# microdevel_actel.net
KiCad netlist of a schematic drawn in Altium Designer
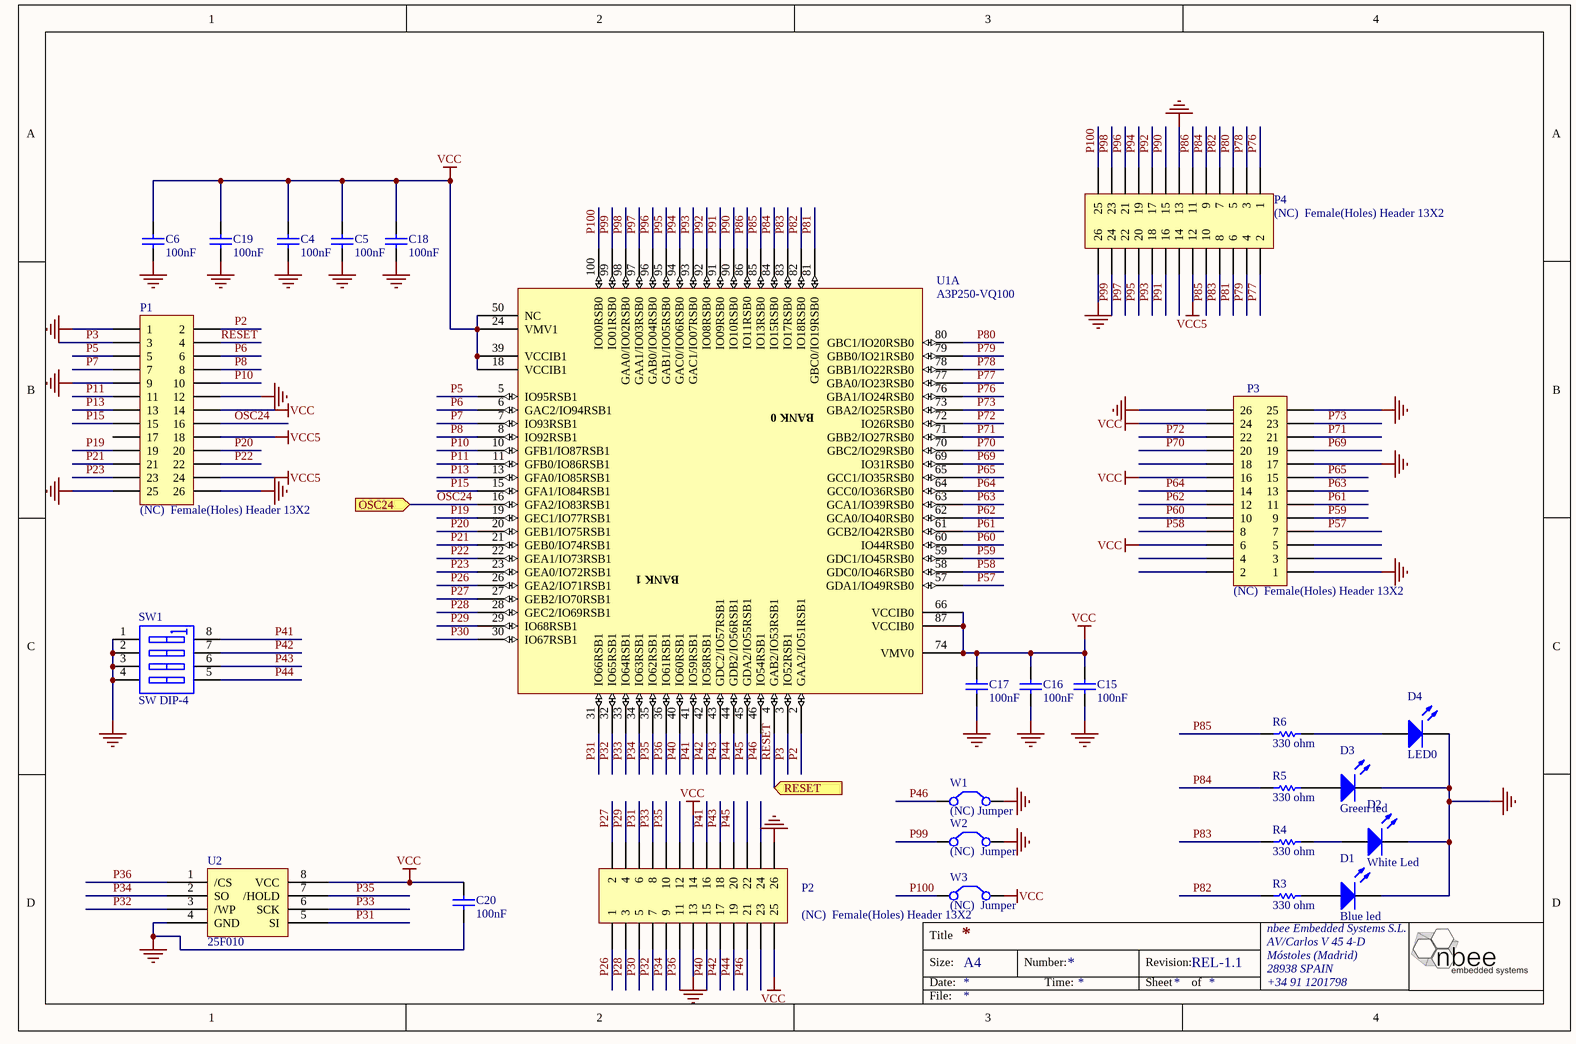
[diagram p0: microdevel_actel.SchDoc]

(export (version "E")
  (design (tool "Eeschema 10.0.6"))
  (components
    (comp (ref "C4")
      (value "100nF")
      (footprint "0603")
      (description "Capacitor (Semiconductor SIM Model)")
      (fields (field (name "PUBLISHER") "Altium Limited"))
      (libsource (lib "Miscellaneous Devices") (part "Cap Semi"))
    )
    (comp (ref "C5")
      (value "100nF")
      (footprint "0603")
      (description "Capacitor (Semiconductor SIM Model)")
      (fields (field (name "PUBLISHER") "Altium Limited"))
      (libsource (lib "Miscellaneous Devices") (part "Cap Semi"))
    )
    (comp (ref "C6")
      (value "100nF")
      (footprint "0603")
      (description "Capacitor (Semiconductor SIM Model)")
      (fields (field (name "PUBLISHER") "Altium Limited"))
      (libsource (lib "Miscellaneous Devices") (part "Cap Semi"))
    )
    (comp (ref "C15")
      (value "100nF")
      (footprint "0603")
      (description "Capacitor (Semiconductor SIM Model)")
      (fields (field (name "PUBLISHER") "Altium Limited"))
      (libsource (lib "Miscellaneous Devices") (part "Cap Semi"))
    )
    (comp (ref "C16")
      (value "100nF")
      (footprint "0603")
      (description "Capacitor (Semiconductor SIM Model)")
      (fields (field (name "PUBLISHER") "Altium Limited"))
      (libsource (lib "Miscellaneous Devices") (part "Cap Semi"))
    )
    (comp (ref "C17")
      (value "100nF")
      (footprint "0603")
      (description "Capacitor (Semiconductor SIM Model)")
      (fields (field (name "PUBLISHER") "Altium Limited"))
      (libsource (lib "Miscellaneous Devices") (part "Cap Semi"))
    )
    (comp (ref "C18")
      (value "100nF")
      (footprint "0603")
      (description "Capacitor (Semiconductor SIM Model)")
      (fields (field (name "PUBLISHER") "Altium Limited"))
      (libsource (lib "Miscellaneous Devices") (part "Cap Semi"))
    )
    (comp (ref "C19")
      (value "100nF")
      (footprint "0603")
      (description "Capacitor (Semiconductor SIM Model)")
      (fields (field (name "PUBLISHER") "Altium Limited"))
      (libsource (lib "Miscellaneous Devices") (part "Cap Semi"))
    )
    (comp (ref "C20")
      (value "100nF")
      (footprint "0603")
      (description "Capacitor (Semiconductor SIM Model)")
      (fields (field (name "PUBLISHER") "Altium Limited"))
      (libsource (lib "Miscellaneous Devices") (part "Cap Semi"))
    )
    (comp (ref "D1")
      (value "Blue led")
      (footprint "LED_0603")
      (description "Typical INFRARED GaAs LED")
      (fields (field (name "PUBLISHER") "Altium Limited"))
      (libsource (lib "Miscellaneous Devices") (part "LED0"))
    )
    (comp (ref "D2")
      (value "White Led")
      (footprint "LED_0603")
      (description "Typical INFRARED GaAs LED")
      (fields (field (name "PUBLISHER") "Altium Limited"))
      (libsource (lib "Miscellaneous Devices") (part "LED0"))
    )
    (comp (ref "D3")
      (value "Green led")
      (footprint "LED_0603")
      (description "Typical INFRARED GaAs LED")
      (fields (field (name "PUBLISHER") "Altium Limited"))
      (libsource (lib "Miscellaneous Devices") (part "LED0"))
    )
    (comp (ref "D4")
      (value "LED0")
      (footprint "LED_0603")
      (description "Red Led")
      (fields (field (name "PUBLISHER") "Altium Limited"))
      (libsource (lib "Miscellaneous Devices") (part "LED0"))
    )
    (comp (ref "P1")
      (value "(NC)  Female(Holes) Header 13X2")
      (footprint "HDR2X13")
      (description "Header, 13-Pin, Dual row")
      (fields (field (name "PUBLISHER") "Altium Limited"))
      (libsource (lib "") (part "Header 13X2_1"))
    )
    (comp (ref "P2")
      (value "(NC)  Female(Holes) Header 13X2")
      (footprint "HDR2X13")
      (description "Header, 13-Pin, Dual row")
      (fields (field (name "PUBLISHER") "Altium Limited"))
      (libsource (lib "Miscellaneous Connectors") (part "Header 13X2"))
    )
    (comp (ref "P3")
      (value "(NC)  Female(Holes) Header 13X2")
      (footprint "HDR2X13")
      (description "Header, 13-Pin, Dual row")
      (fields (field (name "PUBLISHER") "Altium Limited"))
      (libsource (lib "") (part "Header 13X2_2"))
    )
    (comp (ref "P4")
      (value "(NC)  Female(Holes) Header 13X2")
      (footprint "HDR2X13")
      (description "Header, 13-Pin, Dual row")
      (fields (field (name "PUBLISHER") "Altium Limited"))
      (libsource (lib "") (part "Header 13X2_3"))
    )
    (comp (ref "R3")
      (value "330 ohm")
      (footprint "0603")
      (description "Resistor")
      (fields (field (name "PUBLISHER") "Altium Limited"))
      (libsource (lib "Miscellaneous Devices") (part "Res1"))
    )
    (comp (ref "R4")
      (value "330 ohm")
      (footprint "0603")
      (description "Resistor")
      (fields (field (name "PUBLISHER") "Altium Limited"))
      (libsource (lib "Miscellaneous Devices") (part "Res1"))
    )
    (comp (ref "R5")
      (value "330 ohm")
      (footprint "0603")
      (description "Resistor")
      (fields (field (name "PUBLISHER") "Altium Limited"))
      (libsource (lib "Miscellaneous Devices") (part "Res1"))
    )
    (comp (ref "R6")
      (value "330 ohm")
      (footprint "0603")
      (description "Resistor")
      (fields (field (name "PUBLISHER") "Altium Limited"))
      (libsource (lib "Miscellaneous Devices") (part "Res1"))
    )
    (comp (ref "SW1")
      (value "SW DIP-4")
      (footprint "SO8")
      (description "DIP Switch, 4 Position, SPST")
      (fields (field (name "PUBLISHER") "Altium Limited"))
      (libsource (lib "Miscellaneous Devices") (part "SW DIP-4"))
    )
    (comp (ref "U1")
      (value "A3P250-VQ100")
      (footprint "VQ100")
      (fields (field (name "PUBLISHER") "Altium Limited"))
      (libsource (lib "Actel ProASIC3") (part "A3P060-1VQ100"))
    )
    (comp (ref "U2") (value "25F010") (footprint "8S1") (libsource (lib "Schlib1") (part "25F010")))
    (comp (ref "W1")
      (value "(NC) Jumper")
      (footprint "JUMPER")
      (description "Jumper Wire")
      (fields (field (name "PUBLISHER") "Altium Limited"))
      (libsource (lib "Miscellaneous Devices") (part "Jumper"))
    )
    (comp (ref "W2")
      (value "(NC)  Jumper")
      (description "Jumper Wire")
      (fields (field (name "PUBLISHER") "Altium Limited"))
      (libsource (lib "Miscellaneous Devices") (part "Jumper"))
    )
    (comp (ref "W3")
      (value "(NC)  Jumper")
      (description "Jumper Wire")
      (fields (field (name "PUBLISHER") "Altium Limited"))
      (libsource (lib "Miscellaneous Devices") (part "Jumper"))
    )
  )
  (nets
    (net (code "1") (name "/OSC24") (class "Default")
      (node (ref "P1") (pin "16") (pinfunction "16_16") (pintype "passive"))
      (node (ref "U1") (pin "16") (pinfunction "GFA2/IO83RSB1_16") (pintype "bidirectional"))
    )
    (net (code "2") (name "/P2") (class "Default")
      (node (ref "P1") (pin "2") (pinfunction "2_2") (pintype "passive"))
      (node (ref "U1") (pin "2") (pinfunction "GAA2/IO51RSB1_2") (pintype "bidirectional"))
    )
    (net (code "3") (name "/P3") (class "Default")
      (node (ref "P1") (pin "3") (pinfunction "3_3") (pintype "passive"))
      (node (ref "U1") (pin "3") (pinfunction "IO52RSB1_3") (pintype "bidirectional"))
    )
    (net (code "4") (name "/P5") (class "Default")
      (node (ref "P1") (pin "5") (pinfunction "5_5") (pintype "passive"))
      (node (ref "U1") (pin "5") (pinfunction "IO95RSB1_5") (pintype "bidirectional"))
    )
    (net (code "5") (name "/P6") (class "Default")
      (node (ref "P1") (pin "6") (pinfunction "6_6") (pintype "passive"))
      (node (ref "U1") (pin "6") (pinfunction "GAC2/IO94RSB1_6") (pintype "bidirectional"))
    )
    (net (code "6") (name "/P7") (class "Default")
      (node (ref "P1") (pin "7") (pinfunction "7_7") (pintype "passive"))
      (node (ref "U1") (pin "7") (pinfunction "IO93RSB1_7") (pintype "bidirectional"))
    )
    (net (code "7") (name "/P8") (class "Default")
      (node (ref "P1") (pin "8") (pinfunction "8_8") (pintype "passive"))
      (node (ref "U1") (pin "8") (pinfunction "IO92RSB1_8") (pintype "bidirectional"))
    )
    (net (code "8") (name "/P10") (class "Default")
      (node (ref "P1") (pin "10") (pinfunction "10_10") (pintype "passive"))
      (node (ref "U1") (pin "10") (pinfunction "GFB1/IO87RSB1_10") (pintype "bidirectional"))
    )
    (net (code "9") (name "/P11") (class "Default")
      (node (ref "P1") (pin "11") (pinfunction "11_11") (pintype "passive"))
      (node (ref "U1") (pin "11") (pinfunction "GFB0/IO86RSB1_11") (pintype "bidirectional"))
    )
    (net (code "10") (name "/P13") (class "Default")
      (node (ref "P1") (pin "13") (pinfunction "13_13") (pintype "passive"))
      (node (ref "U1") (pin "13") (pinfunction "GFA0/IO85RSB1_13") (pintype "bidirectional"))
    )
    (net (code "11") (name "/P15") (class "Default")
      (node (ref "P1") (pin "15") (pinfunction "15_15") (pintype "passive"))
      (node (ref "U1") (pin "15") (pinfunction "GFA1/IO84RSB1_15") (pintype "bidirectional"))
    )
    (net (code "12") (name "/P19") (class "Default")
      (node (ref "P1") (pin "19") (pinfunction "19_19") (pintype "passive"))
      (node (ref "U1") (pin "19") (pinfunction "GEC1/IO77RSB1_19") (pintype "bidirectional"))
    )
    (net (code "13") (name "/P20") (class "Default")
      (node (ref "P1") (pin "20") (pinfunction "20_20") (pintype "passive"))
      (node (ref "U1") (pin "20") (pinfunction "GEB1/IO75RSB1_20") (pintype "bidirectional"))
    )
    (net (code "14") (name "/P21") (class "Default")
      (node (ref "P1") (pin "21") (pinfunction "21_21") (pintype "passive"))
      (node (ref "U1") (pin "21") (pinfunction "GEB0/IO74RSB1_21") (pintype "bidirectional"))
    )
    (net (code "15") (name "/P22") (class "Default")
      (node (ref "P1") (pin "22") (pinfunction "22_22") (pintype "passive"))
      (node (ref "U1") (pin "22") (pinfunction "GEA1/IO73RSB1_22") (pintype "bidirectional"))
    )
    (net (code "16") (name "/P23") (class "Default")
      (node (ref "P1") (pin "23") (pinfunction "23_23") (pintype "passive"))
      (node (ref "U1") (pin "23") (pinfunction "GEA0/IO72RSB1_23") (pintype "bidirectional"))
    )
    (net (code "17") (name "/P26") (class "Default")
      (node (ref "P2") (pin "1") (pinfunction "1_1") (pintype "passive"))
      (node (ref "U1") (pin "26") (pinfunction "GEA2/IO71RSB1_26") (pintype "bidirectional"))
    )
    (net (code "18") (name "/P27") (class "Default")
      (node (ref "P2") (pin "2") (pinfunction "2_2") (pintype "passive"))
      (node (ref "U1") (pin "27") (pinfunction "GEB2/IO70RSB1_27") (pintype "bidirectional"))
    )
    (net (code "19") (name "/P28") (class "Default")
      (node (ref "P2") (pin "3") (pinfunction "3_3") (pintype "passive"))
      (node (ref "U1") (pin "28") (pinfunction "GEC2/IO69RSB1_28") (pintype "bidirectional"))
    )
    (net (code "20") (name "/P29") (class "Default")
      (node (ref "P2") (pin "4") (pinfunction "4_4") (pintype "passive"))
      (node (ref "U1") (pin "29") (pinfunction "IO68RSB1_29") (pintype "bidirectional"))
    )
    (net (code "21") (name "/P30") (class "Default")
      (node (ref "P2") (pin "5") (pinfunction "5_5") (pintype "passive"))
      (node (ref "U1") (pin "30") (pinfunction "IO67RSB1_30") (pintype "bidirectional"))
    )
    (net (code "22") (name "/P31") (class "Default")
      (node (ref "P2") (pin "6") (pinfunction "6_6") (pintype "passive"))
      (node (ref "U1") (pin "31") (pinfunction "IO66RSB1_31") (pintype "bidirectional"))
      (node (ref "U2") (pin "5") (pinfunction "SI_5") (pintype "passive"))
    )
    (net (code "23") (name "/P32") (class "Default")
      (node (ref "P2") (pin "7") (pinfunction "7_7") (pintype "passive"))
      (node (ref "U1") (pin "32") (pinfunction "IO65RSB1_32") (pintype "bidirectional"))
      (node (ref "U2") (pin "3") (pinfunction "/WP_3") (pintype "passive"))
    )
    (net (code "24") (name "/P33") (class "Default")
      (node (ref "P2") (pin "8") (pinfunction "8_8") (pintype "passive"))
      (node (ref "U1") (pin "33") (pinfunction "IO64RSB1_33") (pintype "bidirectional"))
      (node (ref "U2") (pin "6") (pinfunction "SCK_6") (pintype "passive"))
    )
    (net (code "25") (name "/P34") (class "Default")
      (node (ref "P2") (pin "9") (pinfunction "9_9") (pintype "passive"))
      (node (ref "U1") (pin "34") (pinfunction "IO63RSB1_34") (pintype "bidirectional"))
      (node (ref "U2") (pin "2") (pinfunction "SO_2") (pintype "passive"))
    )
    (net (code "26") (name "/P35") (class "Default")
      (node (ref "P2") (pin "10") (pinfunction "10_10") (pintype "passive"))
      (node (ref "U1") (pin "35") (pinfunction "IO62RSB1_35") (pintype "bidirectional"))
      (node (ref "U2") (pin "7") (pinfunction "/HOLD_7") (pintype "passive"))
    )
    (net (code "27") (name "/P36") (class "Default")
      (node (ref "P2") (pin "11") (pinfunction "11_11") (pintype "passive"))
      (node (ref "U1") (pin "36") (pinfunction "IO61RSB1_36") (pintype "bidirectional"))
      (node (ref "U2") (pin "1") (pinfunction "/CS_1") (pintype "passive"))
    )
    (net (code "28") (name "/P40") (class "Default")
      (node (ref "P2") (pin "15") (pinfunction "15_15") (pintype "passive"))
      (node (ref "U1") (pin "40") (pinfunction "IO60RSB1_40") (pintype "bidirectional"))
    )
    (net (code "29") (name "/P41") (class "Default")
      (node (ref "P2") (pin "16") (pinfunction "16_16") (pintype "passive"))
      (node (ref "SW1") (pin "8") (pinfunction "B1_8") (pintype "passive"))
      (node (ref "U1") (pin "41") (pinfunction "IO59RSB1_41") (pintype "bidirectional"))
    )
    (net (code "30") (name "/P42") (class "Default")
      (node (ref "P2") (pin "17") (pinfunction "17_17") (pintype "passive"))
      (node (ref "SW1") (pin "7") (pinfunction "B2_7") (pintype "passive"))
      (node (ref "U1") (pin "42") (pinfunction "IO58RSB1_42") (pintype "bidirectional"))
    )
    (net (code "31") (name "/P43") (class "Default")
      (node (ref "P2") (pin "18") (pinfunction "18_18") (pintype "passive"))
      (node (ref "SW1") (pin "6") (pinfunction "B3_6") (pintype "passive"))
      (node (ref "U1") (pin "43") (pinfunction "GDC2/IO57RSB1_43") (pintype "bidirectional"))
    )
    (net (code "32") (name "/P44") (class "Default")
      (node (ref "P2") (pin "19") (pinfunction "19_19") (pintype "passive"))
      (node (ref "SW1") (pin "5") (pinfunction "B4_5") (pintype "passive"))
      (node (ref "U1") (pin "44") (pinfunction "GDB2/IO56RSB1_44") (pintype "bidirectional"))
    )
    (net (code "33") (name "/P45") (class "Default")
      (node (ref "P2") (pin "20") (pinfunction "20_20") (pintype "passive"))
      (node (ref "U1") (pin "45") (pinfunction "GDA2/IO55RSB1_45") (pintype "bidirectional"))
    )
    (net (code "34") (name "/P46") (class "Default")
      (node (ref "P2") (pin "21") (pinfunction "21_21") (pintype "passive"))
      (node (ref "U1") (pin "46") (pinfunction "IO54RSB1_46") (pintype "bidirectional"))
      (node (ref "W1") (pin "1") (pinfunction "C1_1") (pintype "passive"))
    )
    (net (code "35") (name "/P57") (class "Default")
      (node (ref "P3") (pin "7") (pinfunction "7_7") (pintype "passive"))
      (node (ref "U1") (pin "57") (pinfunction "GDA1/IO49RSB0_57") (pintype "bidirectional"))
    )
    (net (code "36") (name "/P58") (class "Default")
      (node (ref "P3") (pin "8") (pinfunction "8_8") (pintype "passive"))
      (node (ref "U1") (pin "58") (pinfunction "GDC0/IO46RSB0_58") (pintype "bidirectional"))
    )
    (net (code "37") (name "/P59") (class "Default")
      (node (ref "P3") (pin "9") (pinfunction "9_9") (pintype "passive"))
      (node (ref "U1") (pin "59") (pinfunction "GDC1/IO45RSB0_59") (pintype "bidirectional"))
    )
    (net (code "38") (name "/P60") (class "Default")
      (node (ref "P3") (pin "10") (pinfunction "10_10") (pintype "passive"))
      (node (ref "U1") (pin "60") (pinfunction "IO44RSB0_60") (pintype "bidirectional"))
    )
    (net (code "39") (name "/P61") (class "Default")
      (node (ref "P3") (pin "11") (pinfunction "11_11") (pintype "passive"))
      (node (ref "U1") (pin "61") (pinfunction "GCB2/IO42RSB0_61") (pintype "bidirectional"))
    )
    (net (code "40") (name "/P62") (class "Default")
      (node (ref "P3") (pin "12") (pinfunction "12_12") (pintype "passive"))
      (node (ref "U1") (pin "62") (pinfunction "GCA0/IO40RSB0_62") (pintype "bidirectional"))
    )
    (net (code "41") (name "/P63") (class "Default")
      (node (ref "P3") (pin "13") (pinfunction "13_13") (pintype "passive"))
      (node (ref "U1") (pin "63") (pinfunction "GCA1/IO39RSB0_63") (pintype "bidirectional"))
    )
    (net (code "42") (name "/P64") (class "Default")
      (node (ref "P3") (pin "14") (pinfunction "14_14") (pintype "passive"))
      (node (ref "U1") (pin "64") (pinfunction "GCC0/IO36RSB0_64") (pintype "bidirectional"))
    )
    (net (code "43") (name "/P65") (class "Default")
      (node (ref "P3") (pin "15") (pinfunction "15_15") (pintype "passive"))
      (node (ref "U1") (pin "65") (pinfunction "GCC1/IO35RSB0_65") (pintype "bidirectional"))
    )
    (net (code "44") (name "/P69") (class "Default")
      (node (ref "P3") (pin "19") (pinfunction "19_19") (pintype "passive"))
      (node (ref "U1") (pin "69") (pinfunction "IO31RSB0_69") (pintype "bidirectional"))
    )
    (net (code "45") (name "/P70") (class "Default")
      (node (ref "P3") (pin "20") (pinfunction "20_20") (pintype "passive"))
      (node (ref "U1") (pin "70") (pinfunction "GBC2/IO29RSB0_70") (pintype "bidirectional"))
    )
    (net (code "46") (name "/P71") (class "Default")
      (node (ref "P3") (pin "21") (pinfunction "21_21") (pintype "passive"))
      (node (ref "U1") (pin "71") (pinfunction "GBB2/IO27RSB0_71") (pintype "bidirectional"))
    )
    (net (code "47") (name "/P72") (class "Default")
      (node (ref "P3") (pin "22") (pinfunction "22_22") (pintype "passive"))
      (node (ref "U1") (pin "72") (pinfunction "IO26RSB0_72") (pintype "bidirectional"))
    )
    (net (code "48") (name "/P73") (class "Default")
      (node (ref "P3") (pin "23") (pinfunction "23_23") (pintype "passive"))
      (node (ref "U1") (pin "73") (pinfunction "GBA2/IO25RSB0_73") (pintype "bidirectional"))
    )
    (net (code "49") (name "/P76") (class "Default")
      (node (ref "P4") (pin "1") (pinfunction "1_1") (pintype "passive"))
      (node (ref "U1") (pin "76") (pinfunction "GBA1/IO24RSB0_76") (pintype "bidirectional"))
    )
    (net (code "50") (name "/P77") (class "Default")
      (node (ref "P4") (pin "2") (pinfunction "2_2") (pintype "passive"))
      (node (ref "U1") (pin "77") (pinfunction "GBA0/IO23RSB0_77") (pintype "bidirectional"))
    )
    (net (code "51") (name "/P78") (class "Default")
      (node (ref "P4") (pin "3") (pinfunction "3_3") (pintype "passive"))
      (node (ref "U1") (pin "78") (pinfunction "GBB1/IO22RSB0_78") (pintype "bidirectional"))
    )
    (net (code "52") (name "/P79") (class "Default")
      (node (ref "P4") (pin "4") (pinfunction "4_4") (pintype "passive"))
      (node (ref "U1") (pin "79") (pinfunction "GBB0/IO21RSB0_79") (pintype "bidirectional"))
    )
    (net (code "53") (name "/P80") (class "Default")
      (node (ref "P4") (pin "5") (pinfunction "5_5") (pintype "passive"))
      (node (ref "U1") (pin "80") (pinfunction "GBC1/IO20RSB0_80") (pintype "bidirectional"))
    )
    (net (code "54") (name "/P81") (class "Default")
      (node (ref "P4") (pin "6") (pinfunction "6_6") (pintype "passive"))
      (node (ref "U1") (pin "81") (pinfunction "GBC0/IO19RSB0_81") (pintype "bidirectional"))
    )
    (net (code "55") (name "/P82") (class "Default")
      (node (ref "P4") (pin "7") (pinfunction "7_7") (pintype "passive"))
      (node (ref "R3") (pin "2") (pinfunction "2_2") (pintype "passive"))
      (node (ref "U1") (pin "82") (pinfunction "IO18RSB0_82") (pintype "bidirectional"))
    )
    (net (code "56") (name "/P83") (class "Default")
      (node (ref "P4") (pin "8") (pinfunction "8_8") (pintype "passive"))
      (node (ref "R4") (pin "2") (pinfunction "2_2") (pintype "passive"))
      (node (ref "U1") (pin "83") (pinfunction "IO17RSB0_83") (pintype "bidirectional"))
    )
    (net (code "57") (name "/P84") (class "Default")
      (node (ref "P4") (pin "9") (pinfunction "9_9") (pintype "passive"))
      (node (ref "R5") (pin "2") (pinfunction "2_2") (pintype "passive"))
      (node (ref "U1") (pin "84") (pinfunction "IO15RSB0_84") (pintype "bidirectional"))
    )
    (net (code "58") (name "/P85") (class "Default")
      (node (ref "P4") (pin "10") (pinfunction "10_10") (pintype "passive"))
      (node (ref "R6") (pin "2") (pinfunction "2_2") (pintype "passive"))
      (node (ref "U1") (pin "85") (pinfunction "IO13RSB0_85") (pintype "bidirectional"))
    )
    (net (code "59") (name "/P86") (class "Default")
      (node (ref "P4") (pin "11") (pinfunction "11_11") (pintype "passive"))
      (node (ref "U1") (pin "86") (pinfunction "IO11RSB0_86") (pintype "bidirectional"))
    )
    (net (code "60") (name "/P90") (class "Default")
      (node (ref "P4") (pin "15") (pinfunction "15_15") (pintype "passive"))
      (node (ref "U1") (pin "90") (pinfunction "IO10RSB0_90") (pintype "bidirectional"))
    )
    (net (code "61") (name "/P91") (class "Default")
      (node (ref "P4") (pin "16") (pinfunction "16_16") (pintype "passive"))
      (node (ref "U1") (pin "91") (pinfunction "IO09RSB0_91") (pintype "bidirectional"))
    )
    (net (code "62") (name "/P92") (class "Default")
      (node (ref "P4") (pin "17") (pinfunction "17_17") (pintype "passive"))
      (node (ref "U1") (pin "92") (pinfunction "IO08RSB0_92") (pintype "bidirectional"))
    )
    (net (code "63") (name "/P93") (class "Default")
      (node (ref "P4") (pin "18") (pinfunction "18_18") (pintype "passive"))
      (node (ref "U1") (pin "93") (pinfunction "GAC1/IO07RSB0_93") (pintype "bidirectional"))
    )
    (net (code "64") (name "/P94") (class "Default")
      (node (ref "P4") (pin "19") (pinfunction "19_19") (pintype "passive"))
      (node (ref "U1") (pin "94") (pinfunction "GAC0/IO06RSB0_94") (pintype "bidirectional"))
    )
    (net (code "65") (name "/P95") (class "Default")
      (node (ref "P4") (pin "20") (pinfunction "20_20") (pintype "passive"))
      (node (ref "U1") (pin "95") (pinfunction "GAB1/IO05RSB0_95") (pintype "bidirectional"))
    )
    (net (code "66") (name "/P96") (class "Default")
      (node (ref "P4") (pin "21") (pinfunction "21_21") (pintype "passive"))
      (node (ref "U1") (pin "96") (pinfunction "GAB0/IO04RSB0_96") (pintype "bidirectional"))
    )
    (net (code "67") (name "/P97") (class "Default")
      (node (ref "P4") (pin "22") (pinfunction "22_22") (pintype "passive"))
      (node (ref "U1") (pin "97") (pinfunction "GAA1/IO03RSB0_97") (pintype "bidirectional"))
    )
    (net (code "68") (name "/P98") (class "Default")
      (node (ref "P4") (pin "23") (pinfunction "23_23") (pintype "passive"))
      (node (ref "U1") (pin "98") (pinfunction "GAA0/IO02RSB0_98") (pintype "bidirectional"))
    )
    (net (code "69") (name "/P99") (class "Default")
      (node (ref "P4") (pin "24") (pinfunction "24_24") (pintype "passive"))
      (node (ref "U1") (pin "99") (pinfunction "IO01RSB0_99") (pintype "bidirectional"))
      (node (ref "W2") (pin "1") (pinfunction "C1_1") (pintype "passive"))
    )
    (net (code "70") (name "/P100") (class "Default")
      (node (ref "P4") (pin "25") (pinfunction "25_25") (pintype "passive"))
      (node (ref "U1") (pin "100") (pinfunction "IO00RSB0_100") (pintype "bidirectional"))
      (node (ref "W3") (pin "1") (pinfunction "C1_1") (pintype "passive"))
    )
    (net (code "71") (name "/RESET") (class "Default")
      (node (ref "P1") (pin "4") (pinfunction "4_4") (pintype "passive"))
      (node (ref "U1") (pin "4") (pinfunction "GAB2/IO53RSB1_4") (pintype "bidirectional"))
    )
    (net (code "72") (name "GND") (class "Default")
      (node (ref "C15") (pin "1") (pinfunction "1_1") (pintype "passive"))
      (node (ref "C16") (pin "1") (pinfunction "1_1") (pintype "passive"))
      (node (ref "C17") (pin "1") (pinfunction "1_1") (pintype "passive"))
      (node (ref "C18") (pin "1") (pinfunction "1_1") (pintype "passive"))
      (node (ref "C19") (pin "1") (pinfunction "1_1") (pintype "passive"))
      (node (ref "C20") (pin "1") (pinfunction "1_1") (pintype "passive"))
      (node (ref "C4") (pin "1") (pinfunction "1_1") (pintype "passive"))
      (node (ref "C5") (pin "1") (pinfunction "1_1") (pintype "passive"))
      (node (ref "C6") (pin "2") (pinfunction "2_2") (pintype "passive"))
      (node (ref "D1") (pin "2") (pinfunction "K_2") (pintype "passive"))
      (node (ref "D2") (pin "2") (pinfunction "K_2") (pintype "passive"))
      (node (ref "D3") (pin "2") (pinfunction "K_2") (pintype "passive"))
      (node (ref "D4") (pin "2") (pinfunction "K_2") (pintype "passive"))
      (node (ref "P1") (pin "1") (pinfunction "1_1") (pintype "passive"))
      (node (ref "P1") (pin "12") (pinfunction "12_12") (pintype "passive"))
      (node (ref "P1") (pin "25") (pinfunction "25_25") (pintype "passive"))
      (node (ref "P1") (pin "26") (pinfunction "26_26") (pintype "passive"))
      (node (ref "P1") (pin "9") (pinfunction "9_9") (pintype "passive"))
      (node (ref "P2") (pin "13") (pinfunction "13_13") (pintype "passive"))
      (node (ref "P2") (pin "26") (pinfunction "26_26") (pintype "passive"))
      (node (ref "P3") (pin "1") (pinfunction "1_1") (pintype "passive"))
      (node (ref "P3") (pin "17") (pinfunction "17_17") (pintype "passive"))
      (node (ref "P3") (pin "25") (pinfunction "25_25") (pintype "passive"))
      (node (ref "P3") (pin "26") (pinfunction "26_26") (pintype "passive"))
      (node (ref "P4") (pin "13") (pinfunction "13_13") (pintype "passive"))
      (node (ref "P4") (pin "26") (pinfunction "26_26") (pintype "passive"))
      (node (ref "SW1") (pin "1") (pinfunction "A1_1") (pintype "passive"))
      (node (ref "SW1") (pin "2") (pinfunction "A2_2") (pintype "passive"))
      (node (ref "SW1") (pin "3") (pinfunction "A3_3") (pintype "passive"))
      (node (ref "SW1") (pin "4") (pinfunction "A4_4") (pintype "passive"))
      (node (ref "U2") (pin "4") (pinfunction "GND_4") (pintype "passive"))
      (node (ref "W1") (pin "2") (pinfunction "C2_2") (pintype "passive"))
      (node (ref "W2") (pin "2") (pinfunction "C2_2") (pintype "passive"))
    )
    (net (code "73") (name "Net-(D1-A)") (class "Default")
      (node (ref "D1") (pin "1") (pinfunction "A_1") (pintype "passive"))
      (node (ref "R3") (pin "1") (pinfunction "1_1") (pintype "passive"))
    )
    (net (code "74") (name "Net-(D2-A)") (class "Default")
      (node (ref "D2") (pin "1") (pinfunction "A_1") (pintype "passive"))
      (node (ref "R4") (pin "1") (pinfunction "1_1") (pintype "passive"))
    )
    (net (code "75") (name "Net-(D3-A)") (class "Default")
      (node (ref "D3") (pin "1") (pinfunction "A_1") (pintype "passive"))
      (node (ref "R5") (pin "1") (pinfunction "1_1") (pintype "passive"))
    )
    (net (code "76") (name "Net-(D4-A)") (class "Default")
      (node (ref "D4") (pin "1") (pinfunction "A_1") (pintype "passive"))
      (node (ref "R6") (pin "1") (pinfunction "1_1") (pintype "passive"))
    )
    (net (code "77") (name "VCC") (class "Default")
      (node (ref "C15") (pin "2") (pinfunction "2_2") (pintype "passive"))
      (node (ref "C16") (pin "2") (pinfunction "2_2") (pintype "passive"))
      (node (ref "C17") (pin "2") (pinfunction "2_2") (pintype "passive"))
      (node (ref "C18") (pin "2") (pinfunction "2_2") (pintype "passive"))
      (node (ref "C19") (pin "2") (pinfunction "2_2") (pintype "passive"))
      (node (ref "C20") (pin "2") (pinfunction "2_2") (pintype "passive"))
      (node (ref "C4") (pin "2") (pinfunction "2_2") (pintype "passive"))
      (node (ref "C5") (pin "2") (pinfunction "2_2") (pintype "passive"))
      (node (ref "C6") (pin "1") (pinfunction "1_1") (pintype "passive"))
      (node (ref "P1") (pin "14") (pinfunction "14_14") (pintype "passive"))
      (node (ref "P2") (pin "14") (pinfunction "14_14") (pintype "passive"))
      (node (ref "P2") (pin "25") (pinfunction "25_25") (pintype "passive"))
      (node (ref "P3") (pin "16") (pinfunction "16_16") (pintype "passive"))
      (node (ref "P3") (pin "24") (pinfunction "24_24") (pintype "passive"))
      (node (ref "P3") (pin "6") (pinfunction "6_6") (pintype "passive"))
      (node (ref "U1") (pin "18") (pinfunction "VCCIB1_18") (pintype "power_in"))
      (node (ref "U1") (pin "24") (pinfunction "VMV1_24") (pintype "power_in"))
      (node (ref "U1") (pin "39") (pinfunction "VCCIB1_39") (pintype "power_in"))
      (node (ref "U1") (pin "50") (pinfunction "NC_50") (pintype "passive"))
      (node (ref "U1") (pin "66") (pinfunction "VCCIB0_66") (pintype "power_in"))
      (node (ref "U1") (pin "74") (pinfunction "VMV0_74") (pintype "power_in"))
      (node (ref "U1") (pin "87") (pinfunction "VCCIB0_87") (pintype "power_in"))
      (node (ref "U2") (pin "8") (pinfunction "VCC_8") (pintype "passive"))
      (node (ref "W3") (pin "2") (pinfunction "C2_2") (pintype "passive"))
    )
    (net (code "78") (name "VCC5") (class "Default")
      (node (ref "P1") (pin "18") (pinfunction "18_18") (pintype "passive"))
      (node (ref "P1") (pin "24") (pinfunction "24_24") (pintype "passive"))
      (node (ref "P4") (pin "12") (pinfunction "12_12") (pintype "passive"))
    )
    (net (code "79") (name "unconnected-(P1-Pad17)") (class "Default")
      (node (ref "P1") (pin "17") (pinfunction "17_17") (pintype "passive"))
    )
    (net (code "80") (name "unconnected-(P2-Pad12)") (class "Default")
      (node (ref "P2") (pin "12") (pinfunction "12_12") (pintype "passive"))
    )
    (net (code "81") (name "unconnected-(P2-Pad22)") (class "Default")
      (node (ref "P2") (pin "22") (pinfunction "22_22") (pintype "passive"))
    )
    (net (code "82") (name "unconnected-(P2-Pad23)") (class "Default")
      (node (ref "P2") (pin "23") (pinfunction "23_23") (pintype "passive"))
    )
    (net (code "83") (name "unconnected-(P2-Pad24)") (class "Default")
      (node (ref "P2") (pin "24") (pinfunction "24_24") (pintype "passive"))
    )
    (net (code "84") (name "unconnected-(P3-Pad2)") (class "Default")
      (node (ref "P3") (pin "2") (pinfunction "2_2") (pintype "passive"))
    )
    (net (code "85") (name "unconnected-(P3-Pad3)") (class "Default")
      (node (ref "P3") (pin "3") (pinfunction "3_3") (pintype "passive"))
    )
    (net (code "86") (name "unconnected-(P3-Pad4)") (class "Default")
      (node (ref "P3") (pin "4") (pinfunction "4_4") (pintype "passive"))
    )
    (net (code "87") (name "unconnected-(P3-Pad5)") (class "Default")
      (node (ref "P3") (pin "5") (pinfunction "5_5") (pintype "passive"))
    )
    (net (code "88") (name "unconnected-(P3-Pad18)") (class "Default")
      (node (ref "P3") (pin "18") (pinfunction "18_18") (pintype "passive"))
    )
    (net (code "89") (name "unconnected-(P4-Pad14)") (class "Default")
      (node (ref "P4") (pin "14") (pinfunction "14_14") (pintype "passive"))
    )
  )
)
